# HX711_3.net
KiCad netlist of a schematic drawn in Altium Designer
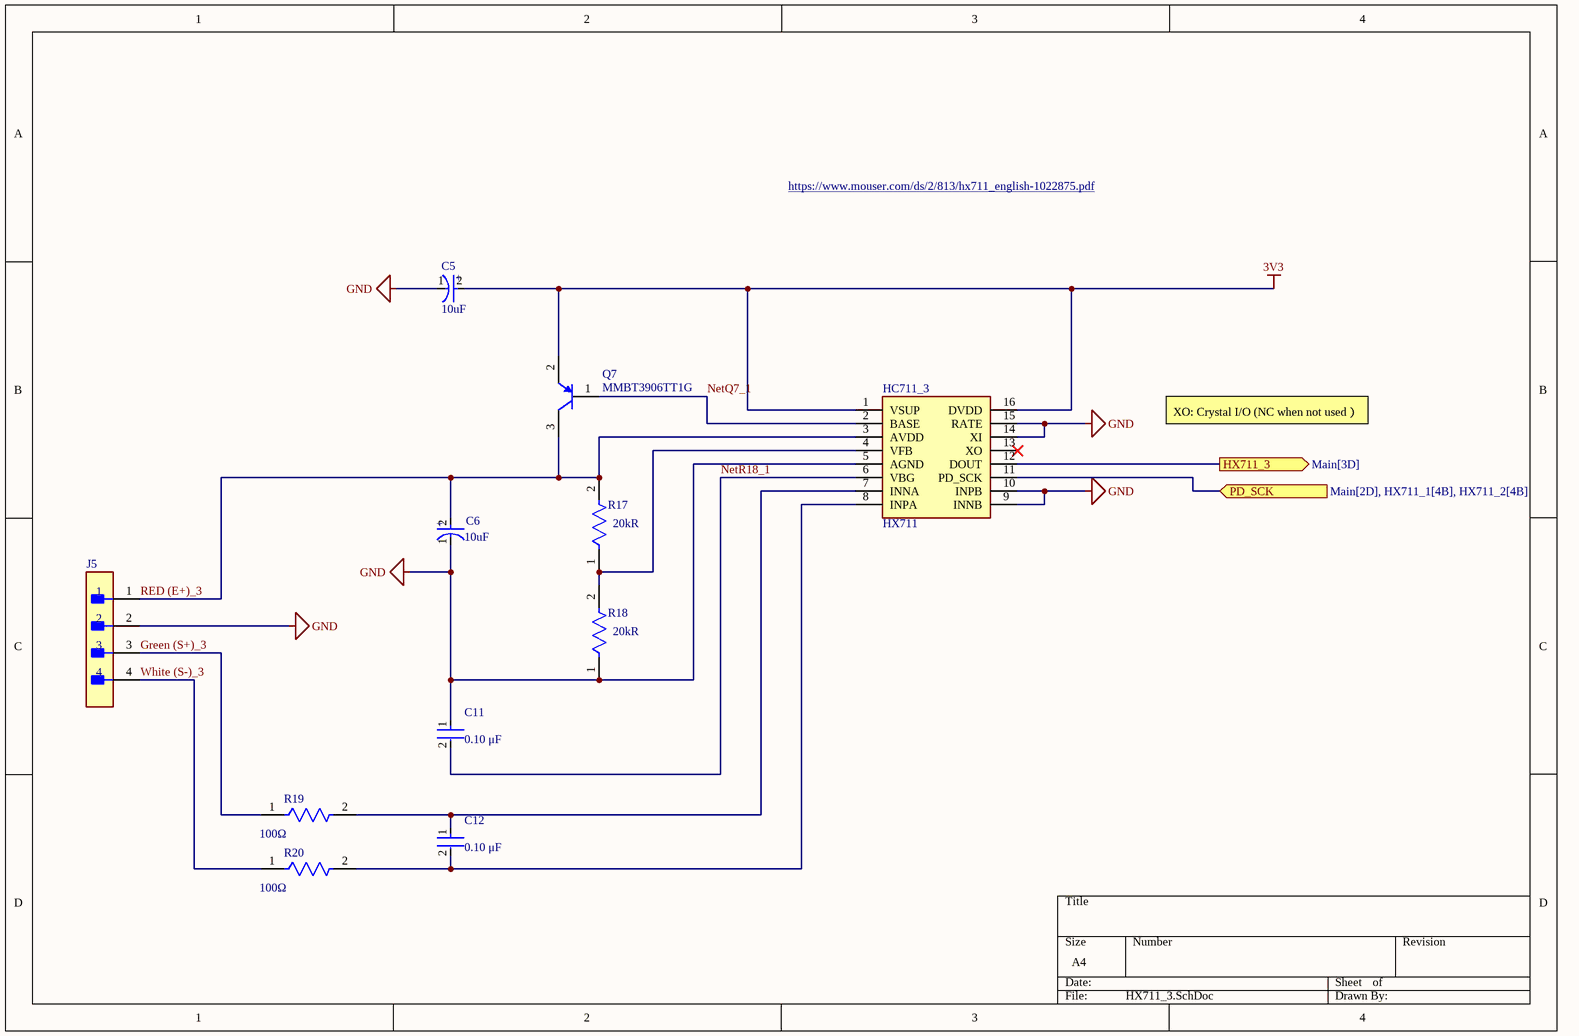
[diagram p0: HX711_3.SchDoc]

(export (version "E")
  (design (tool "Eeschema 10.0.6"))
  (components
    (comp (ref "C5")
      (value "EDK106M035A9BAA")
      (footprint "FP-EDK9B-MFG")
      (description "CAP ALUM 10UF 20% 35V SMD")
      (fields
        (field (name "CAPACITANCE") "10uF")
        (field (name "MANUFACTURER") "Kemet")
        (field (name "OCTOPART") "https://octopart.com/edk106m035a9baa-kemet-26722193")
      )
      (libsource (lib "Altium Content Vault") (part "cf48714ba7e38822c1575c7ec0b6d1f"))
    )
    (comp (ref "C6")
      (value "EDK106M035A9BAA")
      (footprint "FP-EDK9B-MFG")
      (description "CAP ALUM 10UF 20% 35V SMD")
      (fields
        (field (name "CAPACITANCE") "10uF")
        (field (name "MANUFACTURER") "Kemet")
        (field (name "OCTOPART") "https://octopart.com/edk106m035a9baa-kemet-26722193")
      )
      (libsource (lib "Altium Content Vault") (part "cf48714ba7e38822c1575c7ec0b6d1f"))
    )
    (comp (ref "C11")
      (value "0.10 μF")
      (footprint "FP-C0603C-CF-MFG")
      (description "CAP CER 0.1UF 25V X7R 0603")
      (fields
        (field (name "OCTOPART") "https://octopart.com/c0603c104k3rac7411-kemet-9138804")
        (field (name "MANUFACTURER") "KEMET")
      )
      (libsource (lib "Altium Content Vault") (part "b4654b650e69147ec39a6b967a45e02"))
    )
    (comp (ref "C12")
      (value "0.10 μF")
      (footprint "FP-C0603C-CF-MFG")
      (description "CAP CER 0.1UF 25V X7R 0603")
      (fields
        (field (name "OCTOPART") "https://octopart.com/c0603c104k3rac7411-kemet-9138804")
        (field (name "MANUFACTURER") "KEMET")
      )
      (libsource (lib "Altium Content Vault") (part "b4654b650e69147ec39a6b967a45e02"))
    )
    (comp (ref "HC711_3")
      (value "HX711")
      (footprint "SamacSys:SOIC127P600X160-16N")
      (description "Integrated Circuit")
      (libsource (lib "*") (part "HX711"))
    )
    (comp (ref "J5")
      (value "TSW-104-23-T-S")
      (footprint "FP-TSW-104-23-T-S-MFG")
      (description "CONN HEADER VERT 4POS 2.54MM")
      (libsource (lib "Altium Content Vault") (part "f33e0d423099bbb9e64512431cdbdf7"))
    )
    (comp (ref "Q7")
      (value "MMBT3906TT1G")
      (footprint "ONSC-SC-75-3-463-01_V")
      (description "General Purpose Transistor, PNP Silicon, 3-Pin SC-75, Pb-Free, Tape and Reel")
      (fields (field (name "MANUFACTURER") "On Semiconductor"))
      (libsource (lib "Altium Content Vault") (part "ONSC-PNP-B1E2C3-3"))
    )
    (comp (ref "R17")
      (value "CRCW060320K0FKEAHP")
      (footprint "FP-CRCW0603-HPe3-MFG")
      (description "RES Thick Film, 20kΩ, 1%, 0.33W, 100ppm/°C, 0603")
      (fields (field (name "RESISTANCE") "20kR") (field (name "TOLERANCE") "1%"))
      (libsource (lib "Altium Content Vault") (part "1029c3af85768c4190bb7ad29bc67b5"))
    )
    (comp (ref "R18")
      (value "CRCW060320K0FKEAHP")
      (footprint "FP-CRCW0603-HPe3-MFG")
      (description "RES Thick Film, 20kΩ, 1%, 0.33W, 100ppm/°C, 0603")
      (fields (field (name "RESISTANCE") "20kR") (field (name "TOLERANCE") "1%"))
      (libsource (lib "Altium Content Vault") (part "1029c3af85768c4190bb7ad29bc67b5"))
    )
    (comp (ref "R19")
      (value "100Ω")
      (footprint "FP-RT0603-MFG")
      (description "RES SMD 100 OHM 1% 1/10W 0603")
      (fields
        (field (name "MANUFACTURER PART NUMBER") "RT0603FRE07100RL")
        (field (name "MANUFACTURER") "Yageo")
      )
      (libsource (lib "Altium Content Vault") (part "1029c3af85768c4190bb7ad29bc67b5"))
    )
    (comp (ref "R20")
      (value "100Ω")
      (footprint "FP-RT0603-MFG")
      (description "RES SMD 100 OHM 1% 1/10W 0603")
      (fields
        (field (name "MANUFACTURER PART NUMBER") "RT0603FRE07100RL")
        (field (name "MANUFACTURER") "Yageo")
      )
      (libsource (lib "Altium Content Vault") (part "1029c3af85768c4190bb7ad29bc67b5"))
    )
  )
  (nets
    (net (code "1") (name "/Green (S+)_3") (class "Default")
      (node (ref "J5") (pin "3") (pinfunction "3_3") (pintype "passive"))
      (node (ref "R19") (pin "1") (pinfunction "1_1") (pintype "passive"))
    )
    (net (code "2") (name "/HX711_3") (class "Default")
      (node (ref "HC711_3") (pin "12") (pinfunction "DOUT_12") (pintype "passive"))
    )
    (net (code "3") (name "/NetQ7_1") (class "Default")
      (node (ref "HC711_3") (pin "2") (pinfunction "BASE_2") (pintype "passive"))
      (node (ref "Q7") (pin "1") (pinfunction "B_1") (pintype "passive"))
    )
    (net (code "4") (name "/NetR18_1") (class "Default")
      (node (ref "C11") (pin "2") (pinfunction "2_2") (pintype "passive"))
      (node (ref "HC711_3") (pin "6") (pinfunction "VBG_6") (pintype "passive"))
    )
    (net (code "5") (name "/PD_SCK") (class "Default")
      (node (ref "HC711_3") (pin "11") (pinfunction "PD_SCK_11") (pintype "passive"))
    )
    (net (code "6") (name "/RED (E+)_3") (class "Default")
      (node (ref "C6") (pin "2") (pinfunction "A_2") (pintype "passive"))
      (node (ref "HC711_3") (pin "3") (pinfunction "AVDD_3") (pintype "passive"))
      (node (ref "J5") (pin "1") (pinfunction "1_1") (pintype "passive"))
      (node (ref "Q7") (pin "3") (pinfunction "C_3") (pintype "passive"))
      (node (ref "R17") (pin "2") (pinfunction "2_2") (pintype "passive"))
    )
    (net (code "7") (name "/White (S-)_3") (class "Default")
      (node (ref "J5") (pin "4") (pinfunction "4_4") (pintype "passive"))
      (node (ref "R20") (pin "1") (pinfunction "1_1") (pintype "passive"))
    )
    (net (code "8") (name "3V3") (class "Default")
      (node (ref "C5") (pin "2") (pinfunction "A_2") (pintype "passive"))
      (node (ref "HC711_3") (pin "1") (pinfunction "VSUP_1") (pintype "passive"))
      (node (ref "HC711_3") (pin "16") (pinfunction "DVDD_16") (pintype "passive"))
      (node (ref "Q7") (pin "2") (pinfunction "E_2") (pintype "passive"))
    )
    (net (code "9") (name "GND") (class "Default")
      (node (ref "C11") (pin "1") (pinfunction "1_1") (pintype "passive"))
      (node (ref "C5") (pin "1") (pinfunction "C_1") (pintype "passive"))
      (node (ref "C6") (pin "1") (pinfunction "C_1") (pintype "passive"))
      (node (ref "HC711_3") (pin "10") (pinfunction "INPB_10") (pintype "passive"))
      (node (ref "HC711_3") (pin "14") (pinfunction "XI_14") (pintype "passive"))
      (node (ref "HC711_3") (pin "15") (pinfunction "RATE_15") (pintype "passive"))
      (node (ref "HC711_3") (pin "5") (pinfunction "AGND_5") (pintype "passive"))
      (node (ref "HC711_3") (pin "9") (pinfunction "INNB_9") (pintype "passive"))
      (node (ref "J5") (pin "2") (pinfunction "2_2") (pintype "passive"))
      (node (ref "R18") (pin "1") (pinfunction "1_1") (pintype "passive"))
    )
    (net (code "10") (name "Net-(HC711_3-INNA)") (class "Default")
      (node (ref "C12") (pin "1") (pinfunction "1_1") (pintype "passive"))
      (node (ref "HC711_3") (pin "7") (pinfunction "INNA_7") (pintype "passive"))
      (node (ref "R19") (pin "2") (pinfunction "2_2") (pintype "passive"))
    )
    (net (code "11") (name "Net-(HC711_3-INPA)") (class "Default")
      (node (ref "C12") (pin "2") (pinfunction "2_2") (pintype "passive"))
      (node (ref "HC711_3") (pin "8") (pinfunction "INPA_8") (pintype "passive"))
      (node (ref "R20") (pin "2") (pinfunction "2_2") (pintype "passive"))
    )
    (net (code "12") (name "Net-(HC711_3-VFB)") (class "Default")
      (node (ref "HC711_3") (pin "4") (pinfunction "VFB_4") (pintype "passive"))
      (node (ref "R17") (pin "1") (pinfunction "1_1") (pintype "passive"))
      (node (ref "R18") (pin "2") (pinfunction "2_2") (pintype "passive"))
    )
    (net (code "13") (name "unconnected-(HC711_3-XO-Pad13)") (class "Default")
      (node (ref "HC711_3") (pin "13") (pinfunction "XO_13") (pintype "passive+no_connect"))
    )
  )
)
